# gydrodrive_uart.net
KiCad netlist of a schematic drawn in Altium Designer
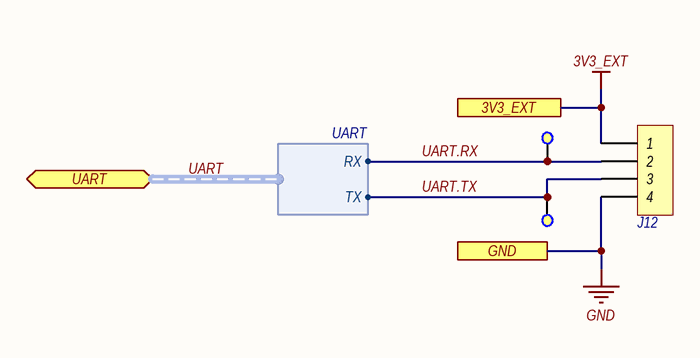
[diagram p0: gydrodrive_uart.SchDoc]

(export (version "E")
  (design (tool "Eeschema 10.0.6"))
  (components
    (comp (ref "J12")
      (value "DG142V-5.08-04P")
      (footprint "DG142V-5.08-04P")
      (description "Клеммник 4-контактный, шаг 5.08 мм")
      (libsource (lib "StdLib") (part "PIN1x4"))
    )
    (comp (ref "TP12")
      (value "Test point 1")
      (footprint "TP_1")
      (description "Тестовый контакт круглый 1 мм")
      (libsource (lib "StdLib") (part "Test point"))
    )
    (comp (ref "TP13")
      (value "Test point 1")
      (footprint "TP_1")
      (description "Тестовый контакт круглый 1 мм")
      (libsource (lib "StdLib") (part "Test point"))
    )
  )
  (nets
    (net (code "2") (name "/UART.RX") (class "Default")
      (node (ref "J12") (pin "2") (pinfunction "2_2") (pintype "passive"))
      (node (ref "TP12") (pin "1") (pinfunction "1_1") (pintype "passive"))
    )
    (net (code "3") (name "/UART.TX") (class "Default")
      (node (ref "J12") (pin "3") (pinfunction "3_3") (pintype "passive"))
      (node (ref "TP13") (pin "1") (pinfunction "1_1") (pintype "passive"))
    )
    (net (code "5") (name "3V3_EXT") (class "Default")
      (node (ref "J12") (pin "1") (pinfunction "1_1") (pintype "passive"))
    )
    (net (code "6") (name "GND") (class "Default")
      (node (ref "J12") (pin "4") (pinfunction "4_4") (pintype "passive"))
    )
  )
)
